# ESP32_Battery_Test_Dec_2025.net
KiCad netlist of a schematic drawn in EasyEDA
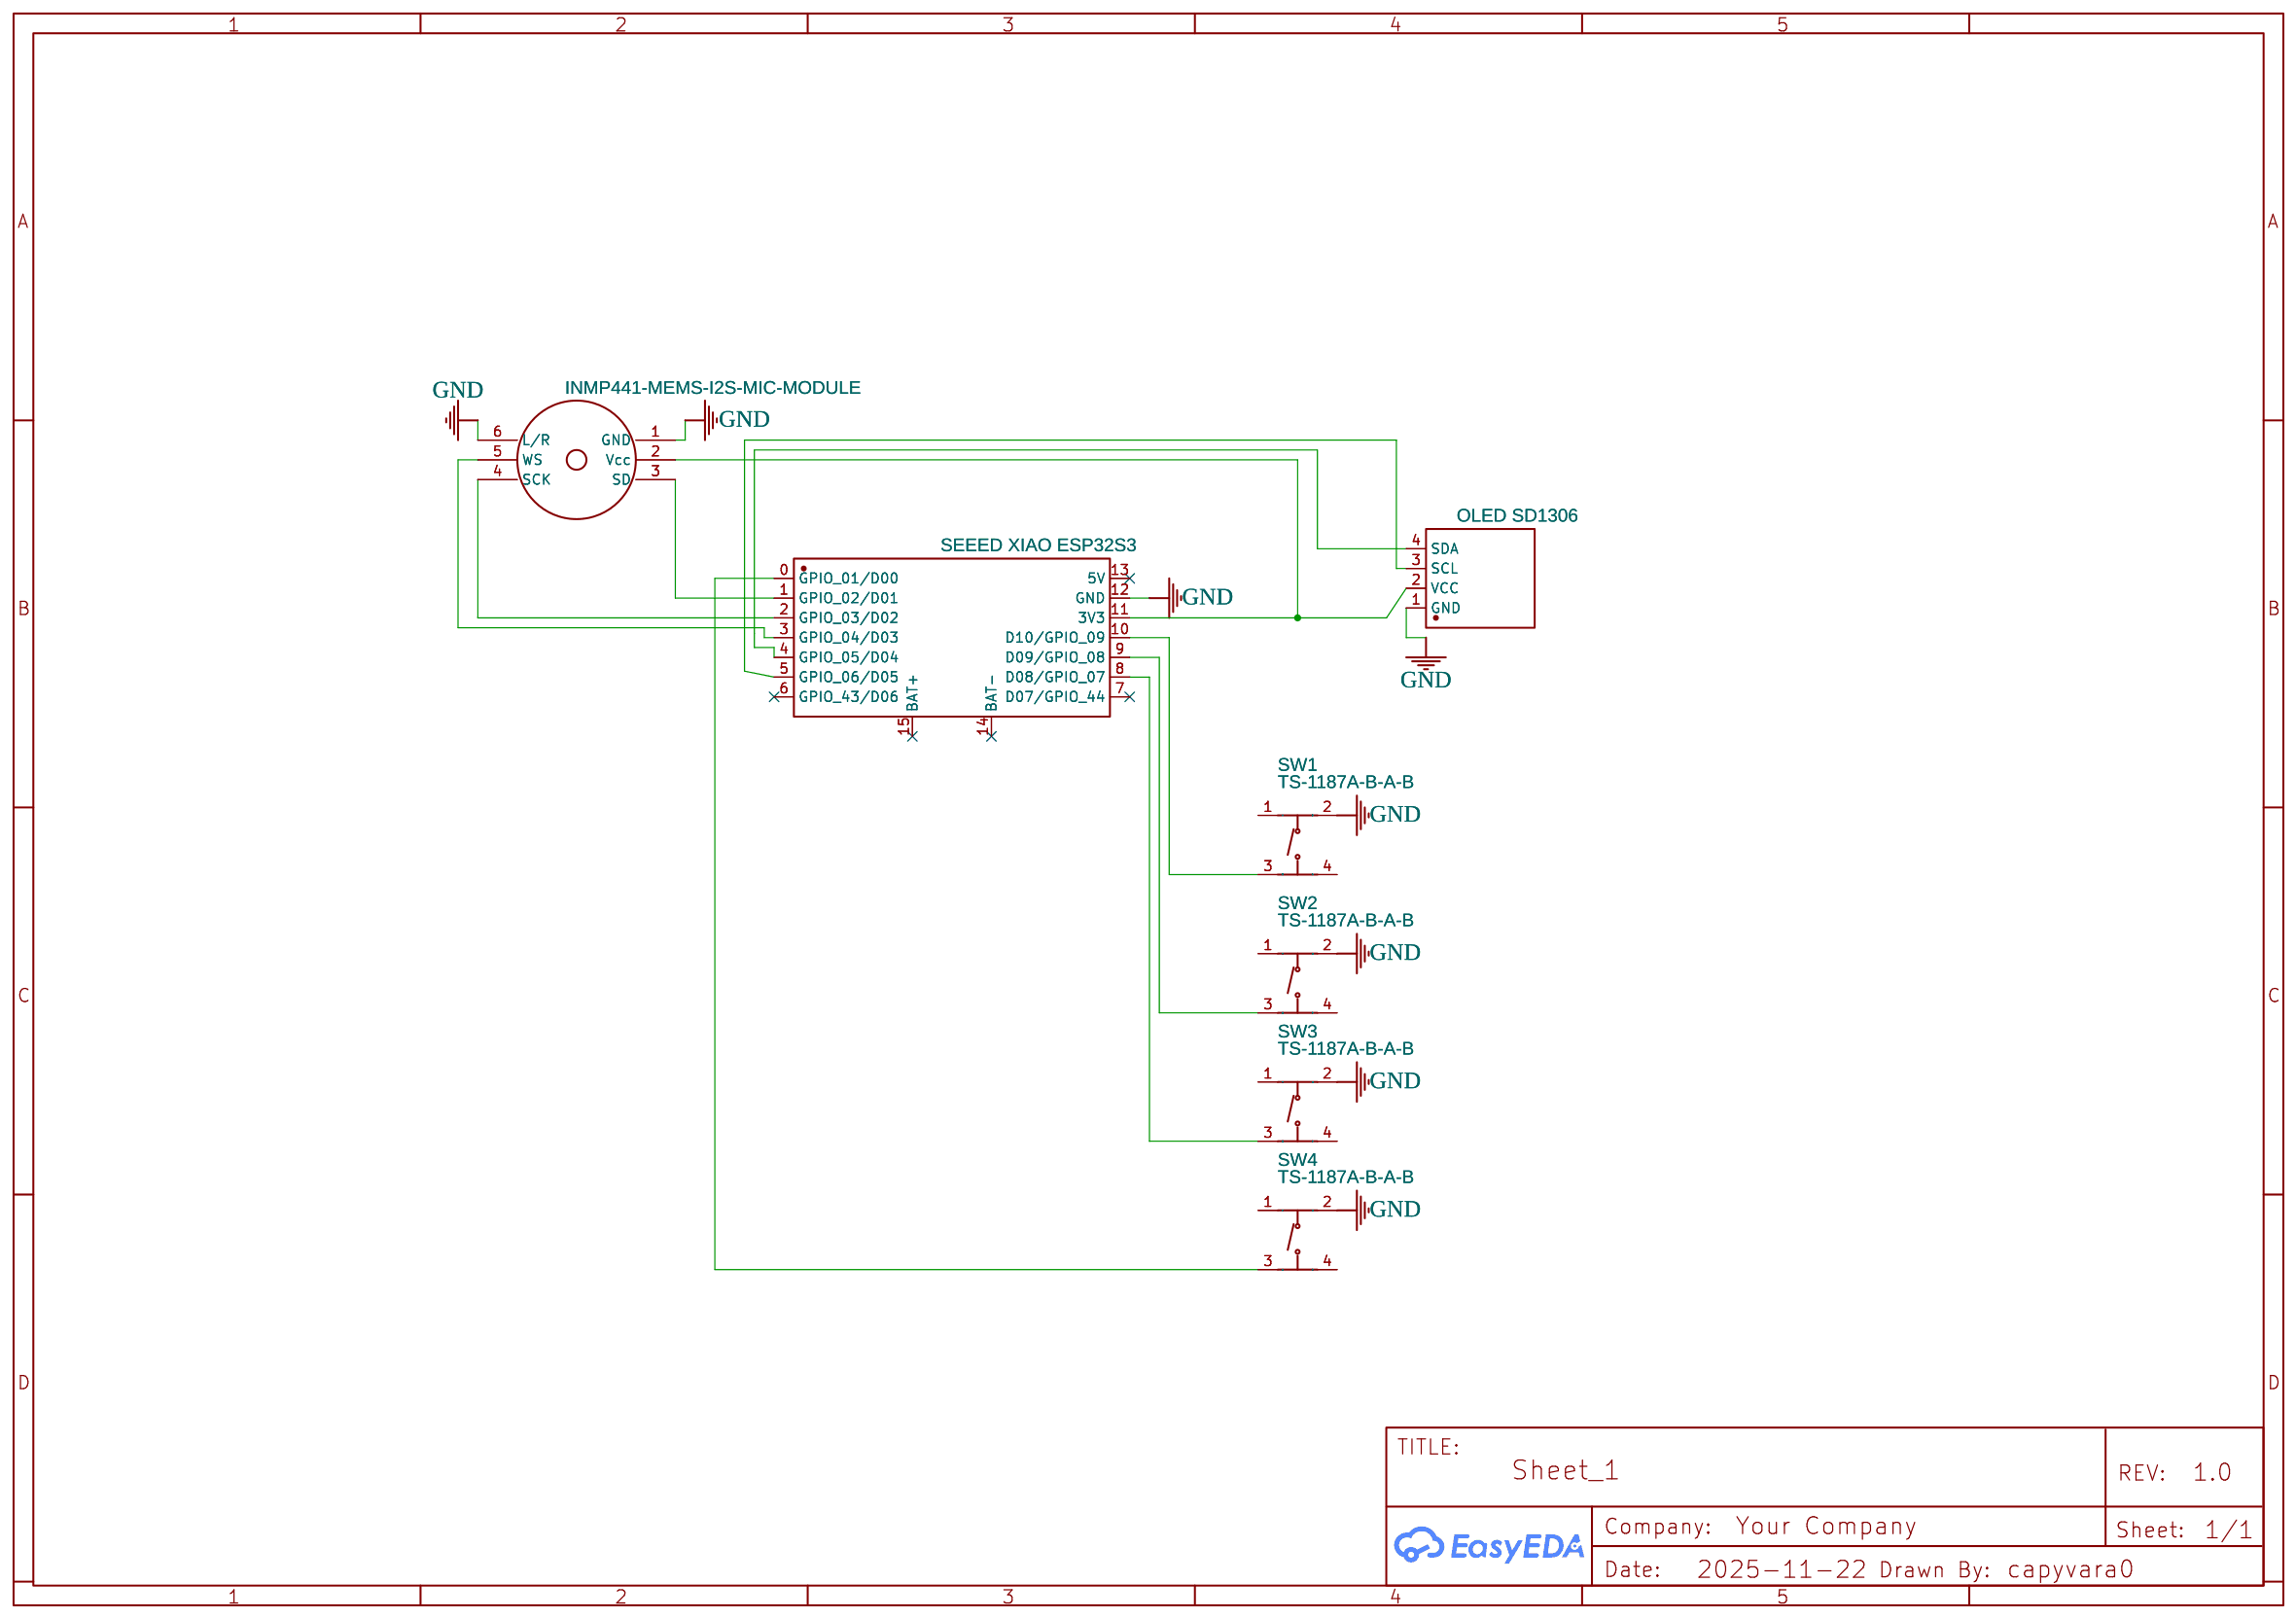
[diagram p0: schematic sheet]

(export (version "E")
  (design (tool "Eeschema 10.0.6"))
  (components
    (comp (ref "SW1")
      (value "TS-1187A-B-A-B")
      (fields (field (name "Manufacturer") "XKB Connection(中国星坤)"))
      (libsource (lib "") (part "TS-1187A-B-A-B"))
    )
    (comp (ref "SW2")
      (value "TS-1187A-B-A-B")
      (fields (field (name "Manufacturer") "XKB Connection(中国星坤)"))
      (libsource (lib "") (part "TS-1187A-B-A-B"))
    )
    (comp (ref "SW3")
      (value "TS-1187A-B-A-B")
      (fields (field (name "Manufacturer") "XKB Connection(中国星坤)"))
      (libsource (lib "") (part "TS-1187A-B-A-B"))
    )
    (comp (ref "SW4")
      (value "TS-1187A-B-A-B")
      (fields (field (name "Manufacturer") "XKB Connection(中国星坤)"))
      (libsource (lib "") (part "TS-1187A-B-A-B"))
    )
    (comp (ref "U1")
      (value "SEEED XIAO ESP32S3")
      (fields (field (name "Manufacturer Part") "Xiao") (field (name "Manufacturer") "Seeeduino"))
      (libsource (lib "") (part "SEEED XIAO ESP32S3"))
    )
    (comp (ref "U2")
      (value "INMP441-MEMS-I2S-MIC-MODULE")
      (libsource (lib "") (part "INMP441-MEMS-I2S-MIC-MODULE"))
    )
    (comp (ref "U4")
      (value "OLED SD1306")
      (fields (field (name "Manufacturer Part") "1.3寸OLED显示屏12864"))
      (libsource (lib "") (part "OLED SD1306"))
    )
  )
  (nets
    (net (code "1") (name "GND") (class "Default")
      (node (ref "SW1") (pin "2") (pinfunction "B_2") (pintype "unspecified"))
      (node (ref "SW2") (pin "2") (pinfunction "B_2") (pintype "unspecified"))
      (node (ref "SW3") (pin "2") (pinfunction "B_2") (pintype "unspecified"))
      (node (ref "SW4") (pin "2") (pinfunction "B_2") (pintype "unspecified"))
      (node (ref "U1") (pin "12") (pinfunction "GND_12") (pintype "unspecified"))
      (node (ref "U2") (pin "1") (pinfunction "GND_1") (pintype "unspecified"))
      (node (ref "U2") (pin "6") (pinfunction "L/R_6") (pintype "unspecified"))
      (node (ref "U4") (pin "1") (pinfunction "GND_1") (pintype "unspecified"))
    )
    (net (code "2") (name "Net-(SW1-C)") (class "Default")
      (node (ref "SW1") (pin "3") (pinfunction "C_3") (pintype "unspecified"))
      (node (ref "U1") (pin "10") (pinfunction "D10/GPIO_09_10") (pintype "unspecified"))
    )
    (net (code "3") (name "Net-(SW2-C)") (class "Default")
      (node (ref "SW2") (pin "3") (pinfunction "C_3") (pintype "unspecified"))
      (node (ref "U1") (pin "9") (pinfunction "D09/GPIO_08_9") (pintype "unspecified"))
    )
    (net (code "4") (name "Net-(SW3-C)") (class "Default")
      (node (ref "SW3") (pin "3") (pinfunction "C_3") (pintype "unspecified"))
      (node (ref "U1") (pin "8") (pinfunction "D08/GPIO_07_8") (pintype "unspecified"))
    )
    (net (code "5") (name "Net-(SW4-C)") (class "Default")
      (node (ref "SW4") (pin "3") (pinfunction "C_3") (pintype "unspecified"))
      (node (ref "U1") (pin "0") (pinfunction "GPIO_01/D00_0") (pintype "unspecified"))
    )
    (net (code "6") (name "Net-(U1-3V3)") (class "Default")
      (node (ref "U1") (pin "11") (pinfunction "3V3_11") (pintype "unspecified"))
      (node (ref "U2") (pin "2") (pinfunction "Vcc_2") (pintype "unspecified"))
      (node (ref "U4") (pin "2") (pinfunction "VCC_2") (pintype "unspecified"))
    )
    (net (code "7") (name "Net-(U1-GPIO_02{slash}D01)") (class "Default")
      (node (ref "U1") (pin "1") (pinfunction "GPIO_02/D01_1") (pintype "unspecified"))
      (node (ref "U2") (pin "3") (pinfunction "SD_3") (pintype "unspecified"))
    )
    (net (code "8") (name "Net-(U1-GPIO_03{slash}D02)") (class "Default")
      (node (ref "U1") (pin "2") (pinfunction "GPIO_03/D02_2") (pintype "unspecified"))
      (node (ref "U2") (pin "4") (pinfunction "SCK_4") (pintype "unspecified"))
    )
    (net (code "9") (name "Net-(U1-GPIO_04{slash}D03)") (class "Default")
      (node (ref "U1") (pin "3") (pinfunction "GPIO_04/D03_3") (pintype "unspecified"))
      (node (ref "U2") (pin "5") (pinfunction "WS_5") (pintype "unspecified"))
    )
    (net (code "10") (name "Net-(U1-GPIO_05{slash}D04)") (class "Default")
      (node (ref "U1") (pin "4") (pinfunction "GPIO_05/D04_4") (pintype "unspecified"))
      (node (ref "U4") (pin "4") (pinfunction "SDA_4") (pintype "unspecified"))
    )
    (net (code "11") (name "Net-(U1-GPIO_06{slash}D05)") (class "Default")
      (node (ref "U1") (pin "5") (pinfunction "GPIO_06/D05_5") (pintype "unspecified"))
      (node (ref "U4") (pin "3") (pinfunction "SCL_3") (pintype "unspecified"))
    )
    (net (code "12") (name "unconnected-(SW1-A-Pad1)") (class "Default")
      (node (ref "SW1") (pin "1") (pinfunction "A_1") (pintype "unspecified"))
    )
    (net (code "13") (name "unconnected-(SW1-D-Pad4)") (class "Default")
      (node (ref "SW1") (pin "4") (pinfunction "D_4") (pintype "unspecified"))
    )
    (net (code "14") (name "unconnected-(SW2-A-Pad1)") (class "Default")
      (node (ref "SW2") (pin "1") (pinfunction "A_1") (pintype "unspecified"))
    )
    (net (code "15") (name "unconnected-(SW2-D-Pad4)") (class "Default")
      (node (ref "SW2") (pin "4") (pinfunction "D_4") (pintype "unspecified"))
    )
    (net (code "16") (name "unconnected-(SW3-A-Pad1)") (class "Default")
      (node (ref "SW3") (pin "1") (pinfunction "A_1") (pintype "unspecified"))
    )
    (net (code "17") (name "unconnected-(SW3-D-Pad4)") (class "Default")
      (node (ref "SW3") (pin "4") (pinfunction "D_4") (pintype "unspecified"))
    )
    (net (code "18") (name "unconnected-(SW4-A-Pad1)") (class "Default")
      (node (ref "SW4") (pin "1") (pinfunction "A_1") (pintype "unspecified"))
    )
    (net (code "19") (name "unconnected-(SW4-D-Pad4)") (class "Default")
      (node (ref "SW4") (pin "4") (pinfunction "D_4") (pintype "unspecified"))
    )
    (net (code "20") (name "unconnected-(U1-5V-Pad13)") (class "Default")
      (node (ref "U1") (pin "13") (pinfunction "5V_13") (pintype "unspecified+no_connect"))
    )
    (net (code "21") (name "unconnected-(U1-BAT+-Pad15)") (class "Default")
      (node (ref "U1") (pin "15") (pinfunction "BAT+_15") (pintype "unspecified+no_connect"))
    )
    (net (code "22") (name "unconnected-(U1-BAT--Pad14)") (class "Default")
      (node (ref "U1") (pin "14") (pinfunction "BAT-_14") (pintype "unspecified+no_connect"))
    )
    (net (code "23") (name "unconnected-(U1-D07{slash}GPIO_44-Pad7)") (class "Default")
      (node (ref "U1") (pin "7") (pinfunction "D07/GPIO_44_7") (pintype "unspecified+no_connect"))
    )
    (net (code "24") (name "unconnected-(U1-GPIO_43{slash}D06-Pad6)") (class "Default")
      (node (ref "U1") (pin "6") (pinfunction "GPIO_43/D06_6") (pintype "unspecified+no_connect"))
    )
  )
)
